# left_board.net
KiCad netlist of a schematic drawn in EAGLE
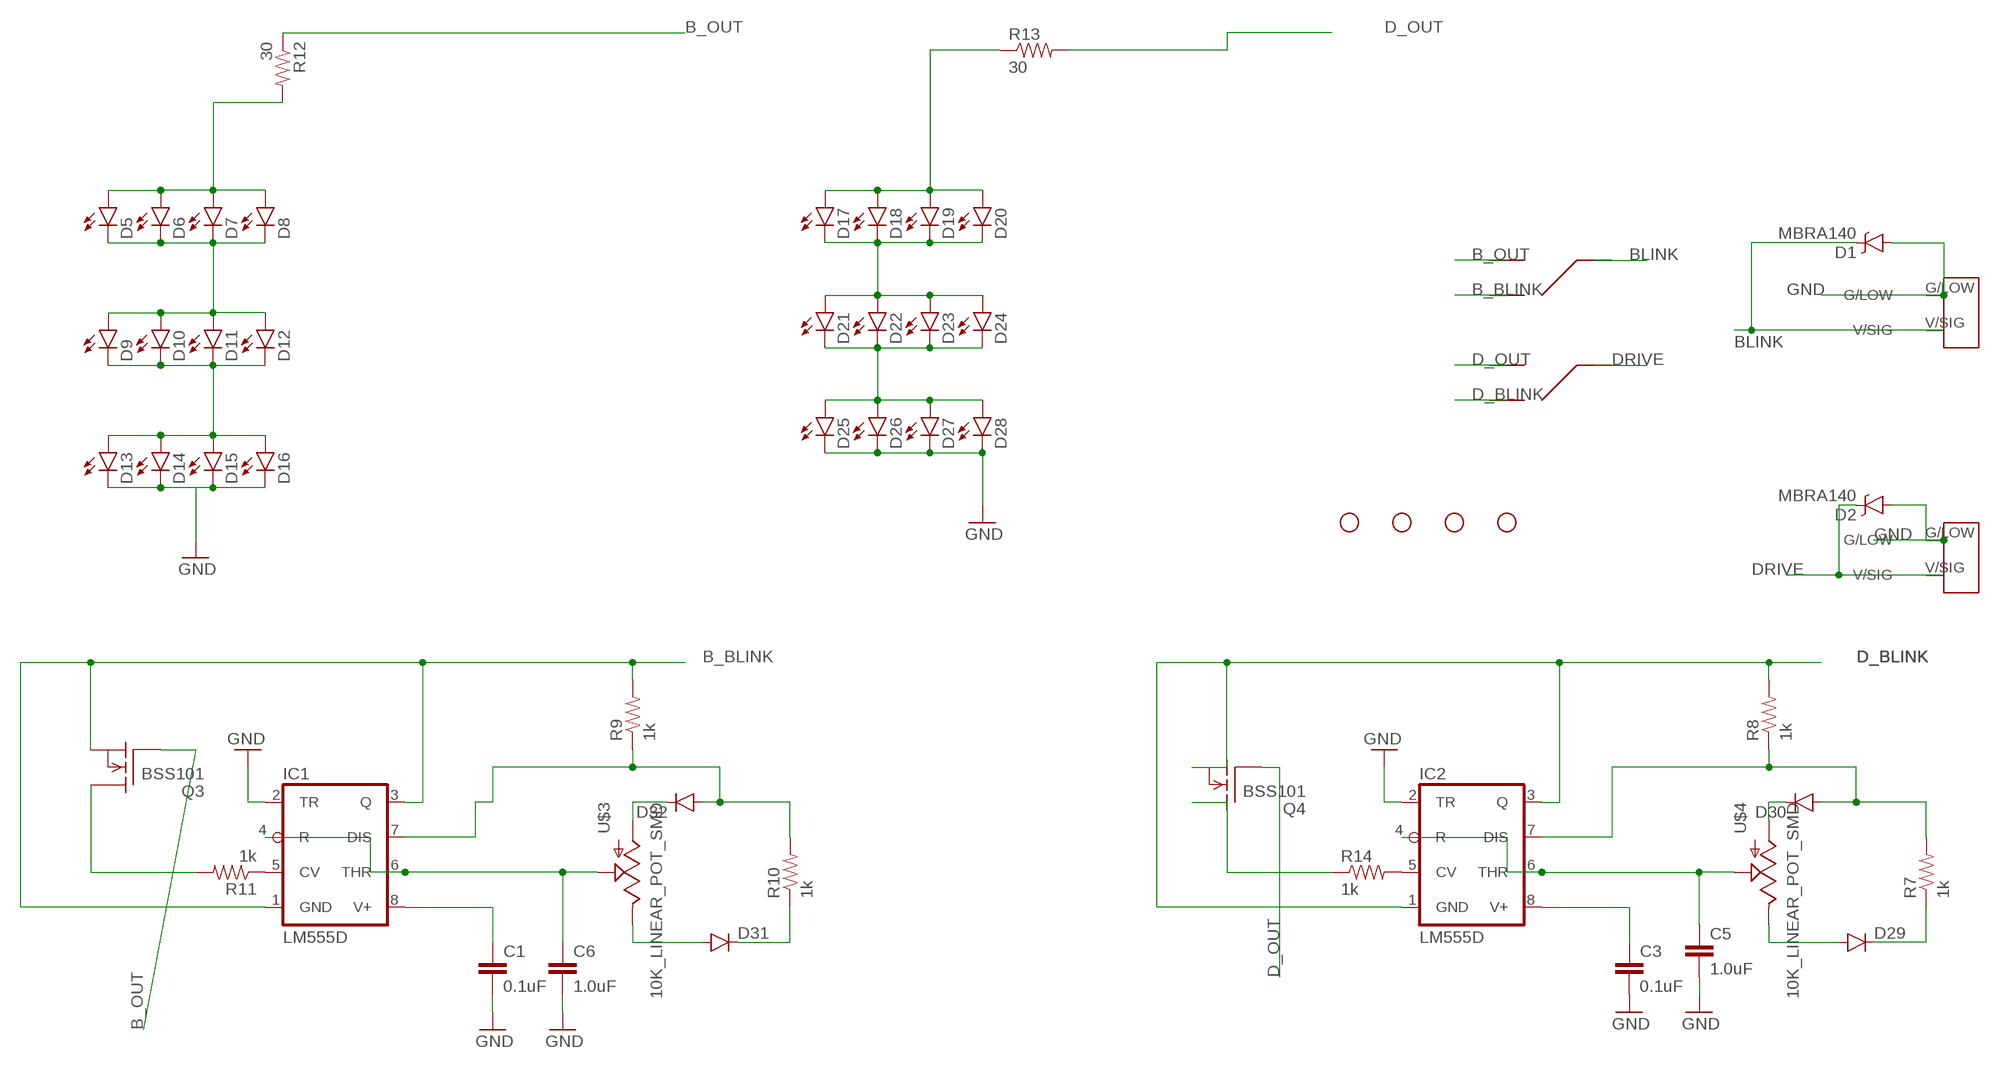
[diagram p0: schematic, sheet 1]

(export (version "E")
  (design (tool "Eeschema 10.0.6"))
  (components
    (comp (ref "C1")
      (value "0.1uF")
      (footprint "eagle-import:0603-CAP")
      (libsource (lib "eagle-import") (part "0.1UF-25V(+80/-20%)(0603)"))
    )
    (comp (ref "C3")
      (value "0.1uF")
      (footprint "eagle-import:0603-CAP")
      (libsource (lib "eagle-import") (part "0.1UF-25V(+80/-20%)(0603)"))
    )
    (comp (ref "C5")
      (value "1.0uF")
      (footprint "eagle-import:0805-CAP")
      (libsource (lib "eagle-import") (part "1.0UF-25V-+80/-20(0805){dblquote}"))
    )
    (comp (ref "C6")
      (value "1.0uF")
      (footprint "eagle-import:0805-CAP")
      (libsource (lib "eagle-import") (part "1.0UF-25V-+80/-20(0805){dblquote}"))
    )
    (comp (ref "D1")
      (value "MBRA140")
      (footprint "eagle-import:SMA-DIODE")
      (libsource (lib "eagle-import") (part "MBRA140"))
    )
    (comp (ref "D2")
      (value "MBRA140")
      (footprint "eagle-import:SMA-DIODE")
      (libsource (lib "eagle-import") (part "MBRA140"))
    )
    (comp (ref "D5")
      (value "LED5MM")
      (footprint "eagle-import:LED5MM")
      (libsource (lib "eagle-import") (part "LED5MM"))
    )
    (comp (ref "D6")
      (value "LED5MM")
      (footprint "eagle-import:LED5MM")
      (libsource (lib "eagle-import") (part "LED5MM"))
    )
    (comp (ref "D7")
      (value "LED5MM")
      (footprint "eagle-import:LED5MM")
      (libsource (lib "eagle-import") (part "LED5MM"))
    )
    (comp (ref "D8")
      (value "LED5MM")
      (footprint "eagle-import:LED5MM")
      (libsource (lib "eagle-import") (part "LED5MM"))
    )
    (comp (ref "D9")
      (value "LED5MM")
      (footprint "eagle-import:LED5MM")
      (libsource (lib "eagle-import") (part "LED5MM"))
    )
    (comp (ref "D10")
      (value "LED5MM")
      (footprint "eagle-import:LED5MM")
      (libsource (lib "eagle-import") (part "LED5MM"))
    )
    (comp (ref "D11")
      (value "LED5MM")
      (footprint "eagle-import:LED5MM")
      (libsource (lib "eagle-import") (part "LED5MM"))
    )
    (comp (ref "D12")
      (value "LED5MM")
      (footprint "eagle-import:LED5MM")
      (libsource (lib "eagle-import") (part "LED5MM"))
    )
    (comp (ref "D13")
      (value "LED5MM")
      (footprint "eagle-import:LED5MM")
      (libsource (lib "eagle-import") (part "LED5MM"))
    )
    (comp (ref "D14")
      (value "LED5MM")
      (footprint "eagle-import:LED5MM")
      (libsource (lib "eagle-import") (part "LED5MM"))
    )
    (comp (ref "D15")
      (value "LED5MM")
      (footprint "eagle-import:LED5MM")
      (libsource (lib "eagle-import") (part "LED5MM"))
    )
    (comp (ref "D16")
      (value "LED5MM")
      (footprint "eagle-import:LED5MM")
      (libsource (lib "eagle-import") (part "LED5MM"))
    )
    (comp (ref "D17")
      (value "LED5MM")
      (footprint "eagle-import:LED5MM")
      (libsource (lib "eagle-import") (part "LED5MM"))
    )
    (comp (ref "D18")
      (value "LED5MM")
      (footprint "eagle-import:LED5MM")
      (libsource (lib "eagle-import") (part "LED5MM"))
    )
    (comp (ref "D19")
      (value "LED5MM")
      (footprint "eagle-import:LED5MM")
      (libsource (lib "eagle-import") (part "LED5MM"))
    )
    (comp (ref "D20")
      (value "LED5MM")
      (footprint "eagle-import:LED5MM")
      (libsource (lib "eagle-import") (part "LED5MM"))
    )
    (comp (ref "D21")
      (value "LED5MM")
      (footprint "eagle-import:LED5MM")
      (libsource (lib "eagle-import") (part "LED5MM"))
    )
    (comp (ref "D22")
      (value "LED5MM")
      (footprint "eagle-import:LED5MM")
      (libsource (lib "eagle-import") (part "LED5MM"))
    )
    (comp (ref "D23")
      (value "LED5MM")
      (footprint "eagle-import:LED5MM")
      (libsource (lib "eagle-import") (part "LED5MM"))
    )
    (comp (ref "D24")
      (value "LED5MM")
      (footprint "eagle-import:LED5MM")
      (libsource (lib "eagle-import") (part "LED5MM"))
    )
    (comp (ref "D25")
      (value "LED5MM")
      (footprint "eagle-import:LED5MM")
      (libsource (lib "eagle-import") (part "LED5MM"))
    )
    (comp (ref "D26")
      (value "LED5MM")
      (footprint "eagle-import:LED5MM")
      (libsource (lib "eagle-import") (part "LED5MM"))
    )
    (comp (ref "D27")
      (value "LED5MM")
      (footprint "eagle-import:LED5MM")
      (libsource (lib "eagle-import") (part "LED5MM"))
    )
    (comp (ref "D28")
      (value "LED5MM")
      (footprint "eagle-import:LED5MM")
      (libsource (lib "eagle-import") (part "LED5MM"))
    )
    (comp (ref "D29")
      (value "DIODESMA")
      (footprint "eagle-import:SMA-DIODE")
      (libsource (lib "eagle-import") (part "DIODESMA"))
    )
    (comp (ref "D30")
      (value "DIODESMA")
      (footprint "eagle-import:SMA-DIODE")
      (libsource (lib "eagle-import") (part "DIODESMA"))
    )
    (comp (ref "D31")
      (value "DIODESMA")
      (footprint "eagle-import:SMA-DIODE")
      (libsource (lib "eagle-import") (part "DIODESMA"))
    )
    (comp (ref "D32")
      (value "DIODESMA")
      (footprint "eagle-import:SMA-DIODE")
      (libsource (lib "eagle-import") (part "DIODESMA"))
    )
    (comp (ref "H1")
      (value "STAND-OFF")
      (footprint "eagle-import:STAND-OFF")
      (libsource (lib "eagle-import") (part "STAND-OFF"))
    )
    (comp (ref "H2")
      (value "STAND-OFF")
      (footprint "eagle-import:STAND-OFF")
      (libsource (lib "eagle-import") (part "STAND-OFF"))
    )
    (comp (ref "H3")
      (value "STAND-OFF")
      (footprint "eagle-import:STAND-OFF")
      (libsource (lib "eagle-import") (part "STAND-OFF"))
    )
    (comp (ref "H4")
      (value "STAND-OFF")
      (footprint "eagle-import:STAND-OFF")
      (libsource (lib "eagle-import") (part "STAND-OFF"))
    )
    (comp (ref "IC1")
      (value "LM555D")
      (footprint "eagle-import:SO08")
      (libsource (lib "eagle-import") (part "555DLM"))
    )
    (comp (ref "IC2")
      (value "LM555D")
      (footprint "eagle-import:SO08")
      (libsource (lib "eagle-import") (part "555DLM"))
    )
    (comp (ref "Q3")
      (value "BSS101")
      (footprint "eagle-import:TO92")
      (libsource (lib "eagle-import") (part "BSS101"))
    )
    (comp (ref "Q4")
      (value "BSS101")
      (footprint "eagle-import:TO92")
      (libsource (lib "eagle-import") (part "BSS101"))
    )
    (comp (ref "R7")
      (value "1k")
      (footprint "eagle-import:0805")
      (libsource (lib "eagle-import") (part "0.22OHM-1/4W-1%(0805)"))
    )
    (comp (ref "R8")
      (value "1k")
      (footprint "eagle-import:0805")
      (libsource (lib "eagle-import") (part "0.22OHM-1/4W-1%(0805)"))
    )
    (comp (ref "R9")
      (value "1k")
      (footprint "eagle-import:0805")
      (libsource (lib "eagle-import") (part "0.22OHM-1/4W-1%(0805)"))
    )
    (comp (ref "R10")
      (value "1k")
      (footprint "eagle-import:0805")
      (libsource (lib "eagle-import") (part "0.22OHM-1/4W-1%(0805)"))
    )
    (comp (ref "R11")
      (value "1k")
      (footprint "eagle-import:0805")
      (libsource (lib "eagle-import") (part "0.22OHM-1/4W-1%(0805)"))
    )
    (comp (ref "R12")
      (value "30")
      (footprint "eagle-import:0805")
      (libsource (lib "eagle-import") (part "0.22OHM-1/4W-1%(0805)"))
    )
    (comp (ref "R13")
      (value "30")
      (footprint "eagle-import:0805")
      (libsource (lib "eagle-import") (part "0.22OHM-1/4W-1%(0805)"))
    )
    (comp (ref "R14")
      (value "1k")
      (footprint "eagle-import:0805")
      (libsource (lib "eagle-import") (part "0.22OHM-1/4W-1%(0805)"))
    )
    (comp (ref "U$1")
      (value "JS_SERIES_SLIDESWITCCH")
      (footprint "eagle-import:MYPART3")
      (libsource (lib "eagle-import") (part "JS_SERIES_SLIDESWITCCH"))
    )
    (comp (ref "U$2")
      (value "JS_SERIES_SLIDESWITCCH")
      (footprint "eagle-import:MYPART3")
      (libsource (lib "eagle-import") (part "JS_SERIES_SLIDESWITCCH"))
    )
    (comp (ref "U$3")
      (value "10K_LINEAR_POT_SMD")
      (footprint "eagle-import:TC33X")
      (libsource (lib "eagle-import") (part "10K_LINEAR_POT_SMD"))
    )
    (comp (ref "U$4")
      (value "10K_LINEAR_POT_SMD")
      (footprint "eagle-import:TC33X")
      (libsource (lib "eagle-import") (part "10K_LINEAR_POT_SMD"))
    )
    (comp (ref "U$5")
      (value "2_PIN_TECONNECTOR")
      (footprint "eagle-import:2_PIN_CONNECT")
      (libsource (lib "eagle-import") (part "2_PIN_TECONNECTOR"))
    )
    (comp (ref "U$7")
      (value "2_PIN_TECONNECTOR")
      (footprint "eagle-import:2_PIN_CONNECT")
      (libsource (lib "eagle-import") (part "2_PIN_TECONNECTOR"))
    )
  )
  (nets
    (net (code "1") (name "/BLINK") (class "Default")
      (node (ref "D1") (pin "C") (pinfunction "C_C") (pintype "passive"))
      (node (ref "U$1") (pin "IN") (pinfunction "IN_IN") (pintype "bidirectional"))
      (node (ref "U$7") (pin "V/SIG") (pinfunction "V/SIG_V/SIG") (pintype "bidirectional"))
    )
    (net (code "2") (name "/B_BLINK") (class "Default")
      (node (ref "IC1") (pin "1") (pinfunction "GND_1") (pintype "power_in"))
      (node (ref "IC1") (pin "3") (pinfunction "Q_3") (pintype "output"))
      (node (ref "Q3") (pin "1") (pinfunction "S_1") (pintype "passive"))
      (node (ref "R9") (pin "2") (pinfunction "2_2") (pintype "passive"))
      (node (ref "U$1") (pin "OUT1") (pinfunction "OUT1_OUT1") (pintype "bidirectional"))
    )
    (net (code "3") (name "/B_OUT") (class "Default")
      (node (ref "Q3") (pin "2") (pinfunction "G_2") (pintype "passive"))
      (node (ref "R12") (pin "1") (pinfunction "1_1") (pintype "passive"))
      (node (ref "U$1") (pin "OUT2") (pinfunction "OUT2_OUT2") (pintype "bidirectional"))
    )
    (net (code "4") (name "/DRIVE") (class "Default")
      (node (ref "D2") (pin "C") (pinfunction "C_C") (pintype "passive"))
      (node (ref "U$2") (pin "IN") (pinfunction "IN_IN") (pintype "bidirectional"))
      (node (ref "U$5") (pin "V/SIG") (pinfunction "V/SIG_V/SIG") (pintype "bidirectional"))
    )
    (net (code "5") (name "/D_BLINK") (class "Default")
      (node (ref "IC2") (pin "1") (pinfunction "GND_1") (pintype "power_in"))
      (node (ref "IC2") (pin "3") (pinfunction "Q_3") (pintype "output"))
      (node (ref "Q4") (pin "1") (pinfunction "S_1") (pintype "passive"))
      (node (ref "R8") (pin "2") (pinfunction "2_2") (pintype "passive"))
      (node (ref "U$2") (pin "OUT1") (pinfunction "OUT1_OUT1") (pintype "bidirectional"))
    )
    (net (code "6") (name "/D_OUT") (class "Default")
      (node (ref "Q4") (pin "2") (pinfunction "G_2") (pintype "passive"))
      (node (ref "R13") (pin "2") (pinfunction "2_2") (pintype "passive"))
      (node (ref "U$2") (pin "OUT2") (pinfunction "OUT2_OUT2") (pintype "bidirectional"))
    )
    (net (code "7") (name "GND") (class "Default")
      (node (ref "C1") (pin "2") (pinfunction "2_2") (pintype "passive"))
      (node (ref "C3") (pin "2") (pinfunction "2_2") (pintype "passive"))
      (node (ref "C5") (pin "2") (pinfunction "2_2") (pintype "passive"))
      (node (ref "C6") (pin "2") (pinfunction "2_2") (pintype "passive"))
      (node (ref "D1") (pin "A") (pinfunction "A_A") (pintype "passive"))
      (node (ref "D13") (pin "K") (pinfunction "C_K") (pintype "passive"))
      (node (ref "D14") (pin "K") (pinfunction "C_K") (pintype "passive"))
      (node (ref "D15") (pin "K") (pinfunction "C_K") (pintype "passive"))
      (node (ref "D16") (pin "K") (pinfunction "C_K") (pintype "passive"))
      (node (ref "D2") (pin "A") (pinfunction "A_A") (pintype "passive"))
      (node (ref "D25") (pin "K") (pinfunction "C_K") (pintype "passive"))
      (node (ref "D26") (pin "K") (pinfunction "C_K") (pintype "passive"))
      (node (ref "D27") (pin "K") (pinfunction "C_K") (pintype "passive"))
      (node (ref "D28") (pin "K") (pinfunction "C_K") (pintype "passive"))
      (node (ref "IC1") (pin "2") (pinfunction "TR_2") (pintype "input"))
      (node (ref "IC2") (pin "2") (pinfunction "TR_2") (pintype "input"))
      (node (ref "U$5") (pin "G/LOW") (pinfunction "G/LOW_G/LOW") (pintype "bidirectional"))
      (node (ref "U$7") (pin "G/LOW") (pinfunction "G/LOW_G/LOW") (pintype "bidirectional"))
    )
    (net (code "8") (name "Net-(D5-C)") (class "Default")
      (node (ref "D10") (pin "A") (pinfunction "A_A") (pintype "passive"))
      (node (ref "D11") (pin "A") (pinfunction "A_A") (pintype "passive"))
      (node (ref "D12") (pin "A") (pinfunction "A_A") (pintype "passive"))
      (node (ref "D5") (pin "K") (pinfunction "C_K") (pintype "passive"))
      (node (ref "D6") (pin "K") (pinfunction "C_K") (pintype "passive"))
      (node (ref "D7") (pin "K") (pinfunction "C_K") (pintype "passive"))
      (node (ref "D8") (pin "K") (pinfunction "C_K") (pintype "passive"))
      (node (ref "D9") (pin "A") (pinfunction "A_A") (pintype "passive"))
    )
    (net (code "9") (name "Net-(D5-PadA)") (class "Default")
      (node (ref "D5") (pin "A") (pinfunction "A_A") (pintype "passive"))
      (node (ref "D6") (pin "A") (pinfunction "A_A") (pintype "passive"))
      (node (ref "D7") (pin "A") (pinfunction "A_A") (pintype "passive"))
      (node (ref "D8") (pin "A") (pinfunction "A_A") (pintype "passive"))
      (node (ref "R12") (pin "2") (pinfunction "2_2") (pintype "passive"))
    )
    (net (code "10") (name "Net-(D10-C)") (class "Default")
      (node (ref "D10") (pin "K") (pinfunction "C_K") (pintype "passive"))
      (node (ref "D11") (pin "K") (pinfunction "C_K") (pintype "passive"))
      (node (ref "D12") (pin "K") (pinfunction "C_K") (pintype "passive"))
      (node (ref "D13") (pin "A") (pinfunction "A_A") (pintype "passive"))
      (node (ref "D14") (pin "A") (pinfunction "A_A") (pintype "passive"))
      (node (ref "D15") (pin "A") (pinfunction "A_A") (pintype "passive"))
      (node (ref "D16") (pin "A") (pinfunction "A_A") (pintype "passive"))
      (node (ref "D9") (pin "K") (pinfunction "C_K") (pintype "passive"))
    )
    (net (code "11") (name "Net-(D17-C)") (class "Default")
      (node (ref "D17") (pin "K") (pinfunction "C_K") (pintype "passive"))
      (node (ref "D18") (pin "K") (pinfunction "C_K") (pintype "passive"))
      (node (ref "D19") (pin "K") (pinfunction "C_K") (pintype "passive"))
      (node (ref "D20") (pin "K") (pinfunction "C_K") (pintype "passive"))
      (node (ref "D21") (pin "A") (pinfunction "A_A") (pintype "passive"))
      (node (ref "D22") (pin "A") (pinfunction "A_A") (pintype "passive"))
      (node (ref "D23") (pin "A") (pinfunction "A_A") (pintype "passive"))
      (node (ref "D24") (pin "A") (pinfunction "A_A") (pintype "passive"))
    )
    (net (code "12") (name "Net-(D17-PadA)") (class "Default")
      (node (ref "D17") (pin "A") (pinfunction "A_A") (pintype "passive"))
      (node (ref "D18") (pin "A") (pinfunction "A_A") (pintype "passive"))
      (node (ref "D19") (pin "A") (pinfunction "A_A") (pintype "passive"))
      (node (ref "D20") (pin "A") (pinfunction "A_A") (pintype "passive"))
      (node (ref "R13") (pin "1") (pinfunction "1_1") (pintype "passive"))
    )
    (net (code "13") (name "Net-(D21-C)") (class "Default")
      (node (ref "D21") (pin "K") (pinfunction "C_K") (pintype "passive"))
      (node (ref "D22") (pin "K") (pinfunction "C_K") (pintype "passive"))
      (node (ref "D23") (pin "K") (pinfunction "C_K") (pintype "passive"))
      (node (ref "D24") (pin "K") (pinfunction "C_K") (pintype "passive"))
      (node (ref "D25") (pin "A") (pinfunction "A_A") (pintype "passive"))
      (node (ref "D26") (pin "A") (pinfunction "A_A") (pintype "passive"))
      (node (ref "D27") (pin "A") (pinfunction "A_A") (pintype "passive"))
      (node (ref "D28") (pin "A") (pinfunction "A_A") (pintype "passive"))
    )
    (net (code "14") (name "Net-(D29-PadC)") (class "Default")
      (node (ref "D29") (pin "C") (pinfunction "C_C") (pintype "passive"))
      (node (ref "R7") (pin "1") (pinfunction "1_1") (pintype "passive"))
    )
    (net (code "15") (name "Net-(D31-PadC)") (class "Default")
      (node (ref "D31") (pin "C") (pinfunction "C_C") (pintype "passive"))
      (node (ref "R10") (pin "1") (pinfunction "1_1") (pintype "passive"))
    )
    (net (code "16") (name "Net-(IC1-CV)") (class "Default")
      (node (ref "IC1") (pin "5") (pinfunction "CV_5") (pintype "input"))
      (node (ref "R11") (pin "1") (pinfunction "1_1") (pintype "passive"))
    )
    (net (code "17") (name "Net-(IC1-DIS)") (class "Default")
      (node (ref "D32") (pin "A") (pinfunction "A_A") (pintype "passive"))
      (node (ref "IC1") (pin "7") (pinfunction "DIS_7") (pintype "input"))
      (node (ref "R10") (pin "2") (pinfunction "2_2") (pintype "passive"))
      (node (ref "R9") (pin "1") (pinfunction "1_1") (pintype "passive"))
    )
    (net (code "18") (name "Net-(IC1-R)") (class "Default")
      (node (ref "C6") (pin "1") (pinfunction "1_1") (pintype "passive"))
      (node (ref "IC1") (pin "4") (pinfunction "R_4") (pintype "input"))
      (node (ref "IC1") (pin "6") (pinfunction "THR_6") (pintype "input"))
      (node (ref "U$3") (pin "2") (pinfunction "S_2") (pintype "passive"))
    )
    (net (code "19") (name "Net-(IC1-V+)") (class "Default")
      (node (ref "C1") (pin "1") (pinfunction "1_1") (pintype "passive"))
      (node (ref "IC1") (pin "8") (pinfunction "V+_8") (pintype "power_in"))
    )
    (net (code "20") (name "Net-(IC2-CV)") (class "Default")
      (node (ref "IC2") (pin "5") (pinfunction "CV_5") (pintype "input"))
      (node (ref "R14") (pin "2") (pinfunction "2_2") (pintype "passive"))
    )
    (net (code "21") (name "Net-(IC2-DIS)") (class "Default")
      (node (ref "D30") (pin "A") (pinfunction "A_A") (pintype "passive"))
      (node (ref "IC2") (pin "7") (pinfunction "DIS_7") (pintype "input"))
      (node (ref "R7") (pin "2") (pinfunction "2_2") (pintype "passive"))
      (node (ref "R8") (pin "1") (pinfunction "1_1") (pintype "passive"))
    )
    (net (code "22") (name "Net-(IC2-R)") (class "Default")
      (node (ref "C5") (pin "1") (pinfunction "1_1") (pintype "passive"))
      (node (ref "IC2") (pin "4") (pinfunction "R_4") (pintype "input"))
      (node (ref "IC2") (pin "6") (pinfunction "THR_6") (pintype "input"))
      (node (ref "U$4") (pin "2") (pinfunction "S_2") (pintype "passive"))
    )
    (net (code "23") (name "Net-(IC2-V+)") (class "Default")
      (node (ref "C3") (pin "1") (pinfunction "1_1") (pintype "passive"))
      (node (ref "IC2") (pin "8") (pinfunction "V+_8") (pintype "power_in"))
    )
    (net (code "24") (name "Net-(Q3-D)") (class "Default")
      (node (ref "Q3") (pin "3") (pinfunction "D_3") (pintype "passive"))
      (node (ref "R11") (pin "2") (pinfunction "2_2") (pintype "passive"))
    )
    (net (code "25") (name "Net-(Q4-D)") (class "Default")
      (node (ref "Q4") (pin "3") (pinfunction "D_3") (pintype "passive"))
      (node (ref "R14") (pin "1") (pinfunction "1_1") (pintype "passive"))
    )
    (net (code "26") (name "Net-(U$3-A)") (class "Default")
      (node (ref "D32") (pin "C") (pinfunction "C_C") (pintype "passive"))
      (node (ref "U$3") (pin "1") (pinfunction "A_1") (pintype "passive"))
    )
    (net (code "27") (name "Net-(U$3-E)") (class "Default")
      (node (ref "D31") (pin "A") (pinfunction "A_A") (pintype "passive"))
      (node (ref "U$3") (pin "3") (pinfunction "E_3") (pintype "passive"))
    )
    (net (code "28") (name "Net-(U$4-A)") (class "Default")
      (node (ref "D30") (pin "C") (pinfunction "C_C") (pintype "passive"))
      (node (ref "U$4") (pin "1") (pinfunction "A_1") (pintype "passive"))
    )
    (net (code "29") (name "Net-(U$4-E)") (class "Default")
      (node (ref "D29") (pin "A") (pinfunction "A_A") (pintype "passive"))
      (node (ref "U$4") (pin "3") (pinfunction "E_3") (pintype "passive"))
    )
  )
)
